# DC_DC_Convertor.net
KiCad netlist of a schematic drawn in Altium Designer
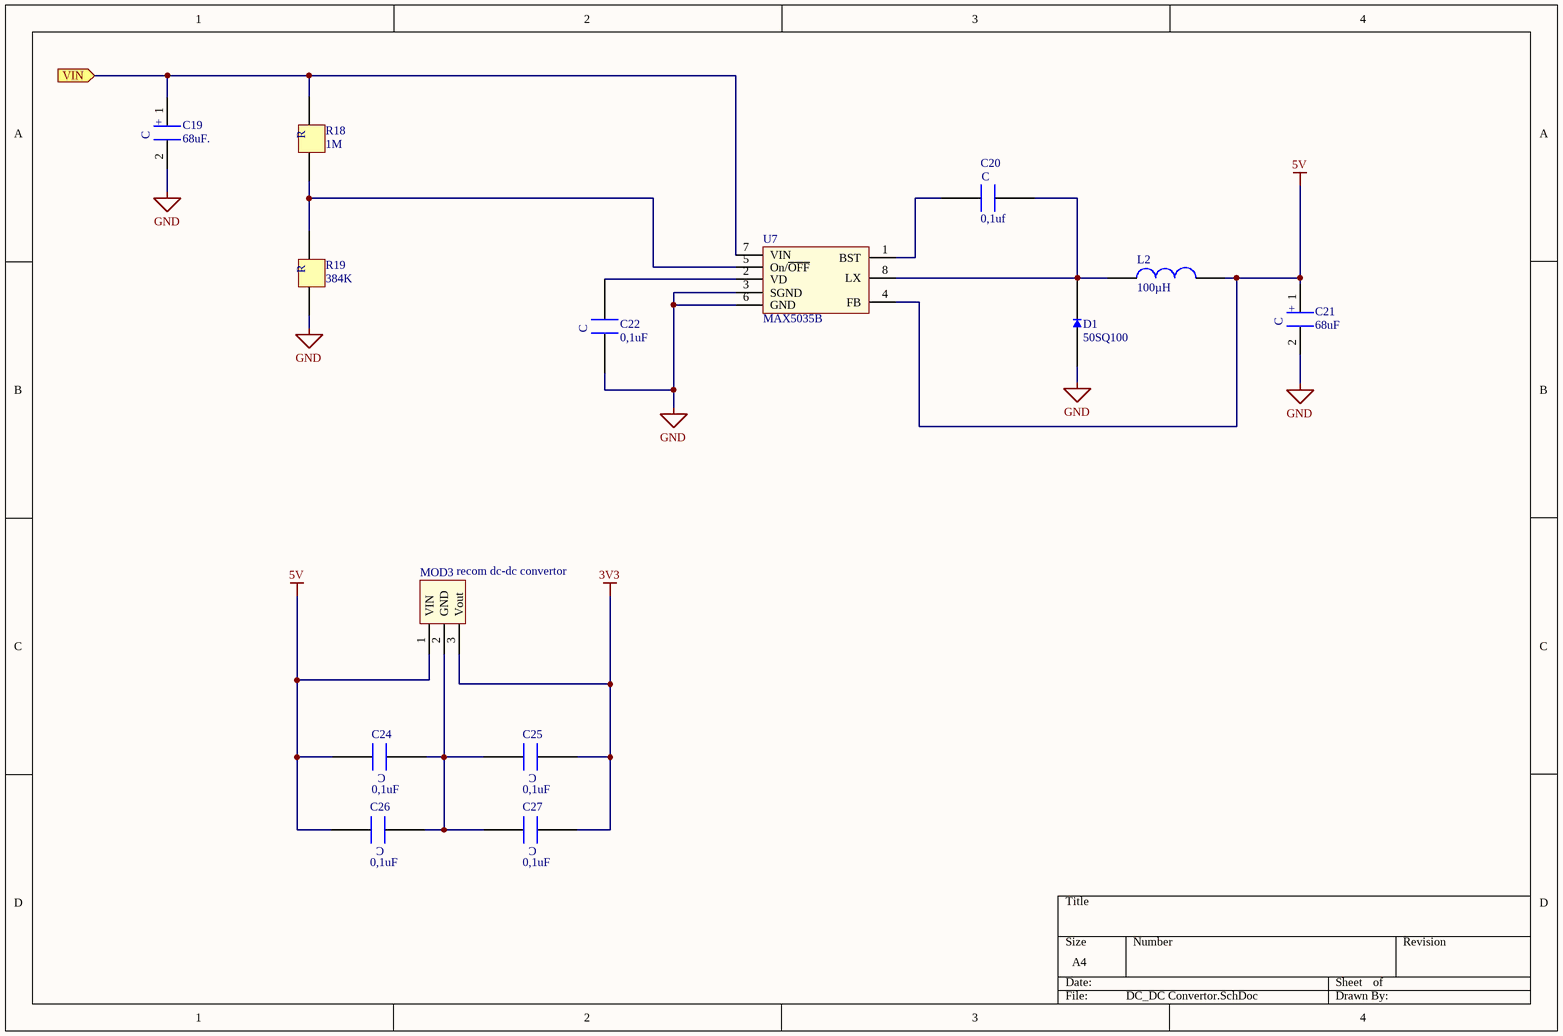
[diagram p0: DC_DC Convertor.SchDoc]

(export (version "E")
  (design (tool "Eeschema 10.0.6"))
  (components
    (comp (ref "C19") (value "68uF.") (libsource (lib "pasives") (part "cap_pol")))
    (comp (ref "C20")
      (value "0,1uf")
      (footprint "CAPC1005X04L")
      (libsource (lib "pasives") (part "capacitor"))
    )
    (comp (ref "C21") (value "68uF") (libsource (lib "pasives") (part "cap_pol")))
    (comp (ref "C22")
      (value "0,1uF")
      (footprint "CAPC1005X04L")
      (libsource (lib "pasives") (part "capacitor"))
    )
    (comp (ref "C24")
      (value "0,1uF")
      (footprint "CAPC1005X04L")
      (libsource (lib "pasives") (part "capacitor"))
    )
    (comp (ref "C25")
      (value "0,1uF")
      (footprint "CAPC1005X04L")
      (libsource (lib "pasives") (part "capacitor"))
    )
    (comp (ref "C26")
      (value "0,1uF")
      (footprint "CAPC1005X04L")
      (libsource (lib "pasives") (part "capacitor"))
    )
    (comp (ref "C27")
      (value "0,1uF")
      (footprint "CAPC1005X04L")
      (libsource (lib "pasives") (part "capacitor"))
    )
    (comp (ref "D1") (value "50SQ100") (footprint "Diode") (libsource (lib "halfgelijders") (part "diode")))
    (comp (ref "L2")
      (value "100µH")
      (footprint "Coilcraft , XFL4020-102")
      (libsource (lib "pasives") (part "Spoel"))
    )
    (comp (ref "MOD3")
      (value "recom dc-dc convertor")
      (libsource (lib "halfgelijders") (part "recom dc-dc convertor"))
    )
    (comp (ref "R18") (value "1M") (footprint "CAPC1005X04L") (libsource (lib "pasives") (part "resistor")))
    (comp (ref "R19") (value "384K") (footprint "CAPC1005X04L") (libsource (lib "pasives") (part "resistor")))
    (comp (ref "U7") (value "MAX5035B") (libsource (lib "halfgelijders") (part "MAX5035")))
  )
  (nets
    (net (code "1") (name "/VIN") (class "Default")
      (node (ref "C19") (pin "1") (pinfunction "1_1") (pintype "passive"))
      (node (ref "R18") (pin "1") (pinfunction "1_1") (pintype "passive"))
      (node (ref "U7") (pin "7") (pinfunction "VIN_7") (pintype "power_in"))
    )
    (net (code "2") (name "3V3") (class "Default")
      (node (ref "C25") (pin "2") (pinfunction "2_2") (pintype "passive"))
      (node (ref "C27") (pin "2") (pinfunction "2_2") (pintype "passive"))
      (node (ref "MOD3") (pin "3") (pinfunction "Vout_3") (pintype "passive"))
    )
    (net (code "3") (name "5V") (class "Default")
      (node (ref "C21") (pin "1") (pinfunction "1_1") (pintype "passive"))
      (node (ref "C24") (pin "1") (pinfunction "1_1") (pintype "passive"))
      (node (ref "C26") (pin "1") (pinfunction "1_1") (pintype "passive"))
      (node (ref "L2") (pin "1") (pinfunction "1_1") (pintype "passive"))
      (node (ref "MOD3") (pin "1") (pinfunction "VIN_1") (pintype "passive"))
      (node (ref "U7") (pin "4") (pinfunction "FB_4") (pintype "passive"))
    )
    (net (code "4") (name "GND") (class "Default")
      (node (ref "C19") (pin "2") (pinfunction "2_2") (pintype "passive"))
      (node (ref "C21") (pin "2") (pinfunction "2_2") (pintype "passive"))
      (node (ref "C22") (pin "2") (pinfunction "2_2") (pintype "passive"))
      (node (ref "D1") (pin "1") (pinfunction "1_1") (pintype "passive"))
      (node (ref "R19") (pin "2") (pinfunction "2_2") (pintype "passive"))
      (node (ref "U7") (pin "3") (pinfunction "SGND_3") (pintype "power_in"))
      (node (ref "U7") (pin "6") (pinfunction "GND_6") (pintype "passive"))
    )
    (net (code "5") (name "Net-(MOD3-GND)") (class "Default")
      (node (ref "C24") (pin "2") (pinfunction "2_2") (pintype "passive"))
      (node (ref "C25") (pin "1") (pinfunction "1_1") (pintype "passive"))
      (node (ref "C26") (pin "2") (pinfunction "2_2") (pintype "passive"))
      (node (ref "C27") (pin "1") (pinfunction "1_1") (pintype "passive"))
      (node (ref "MOD3") (pin "2") (pinfunction "GND_2") (pintype "passive"))
    )
    (net (code "6") (name "Net-(U7-BST)") (class "Default")
      (node (ref "C20") (pin "2") (pinfunction "2_2") (pintype "passive"))
      (node (ref "U7") (pin "1") (pinfunction "BST_1") (pintype "passive"))
    )
    (net (code "7") (name "Net-(U7-LX)") (class "Default")
      (node (ref "C20") (pin "1") (pinfunction "1_1") (pintype "passive"))
      (node (ref "D1") (pin "2") (pinfunction "2_2") (pintype "passive"))
      (node (ref "L2") (pin "2") (pinfunction "2_2") (pintype "passive"))
      (node (ref "U7") (pin "8") (pinfunction "LX_8") (pintype "passive"))
    )
    (net (code "8") (name "Net-(U7-On{slash}~{OFF})") (class "Default")
      (node (ref "R18") (pin "2") (pinfunction "2_2") (pintype "passive"))
      (node (ref "R19") (pin "1") (pinfunction "1_1") (pintype "passive"))
      (node (ref "U7") (pin "5") (pinfunction "On/~{OFF}_5") (pintype "passive"))
    )
    (net (code "9") (name "Net-(U7-VD)") (class "Default")
      (node (ref "C22") (pin "1") (pinfunction "1_1") (pintype "passive"))
      (node (ref "U7") (pin "2") (pinfunction "VD_2") (pintype "passive"))
    )
  )
)
